# ProPrj_MP2456_2024-10-30_10-07-32_2024-1.net
KiCad netlist of a schematic drawn in EasyEDA Pro
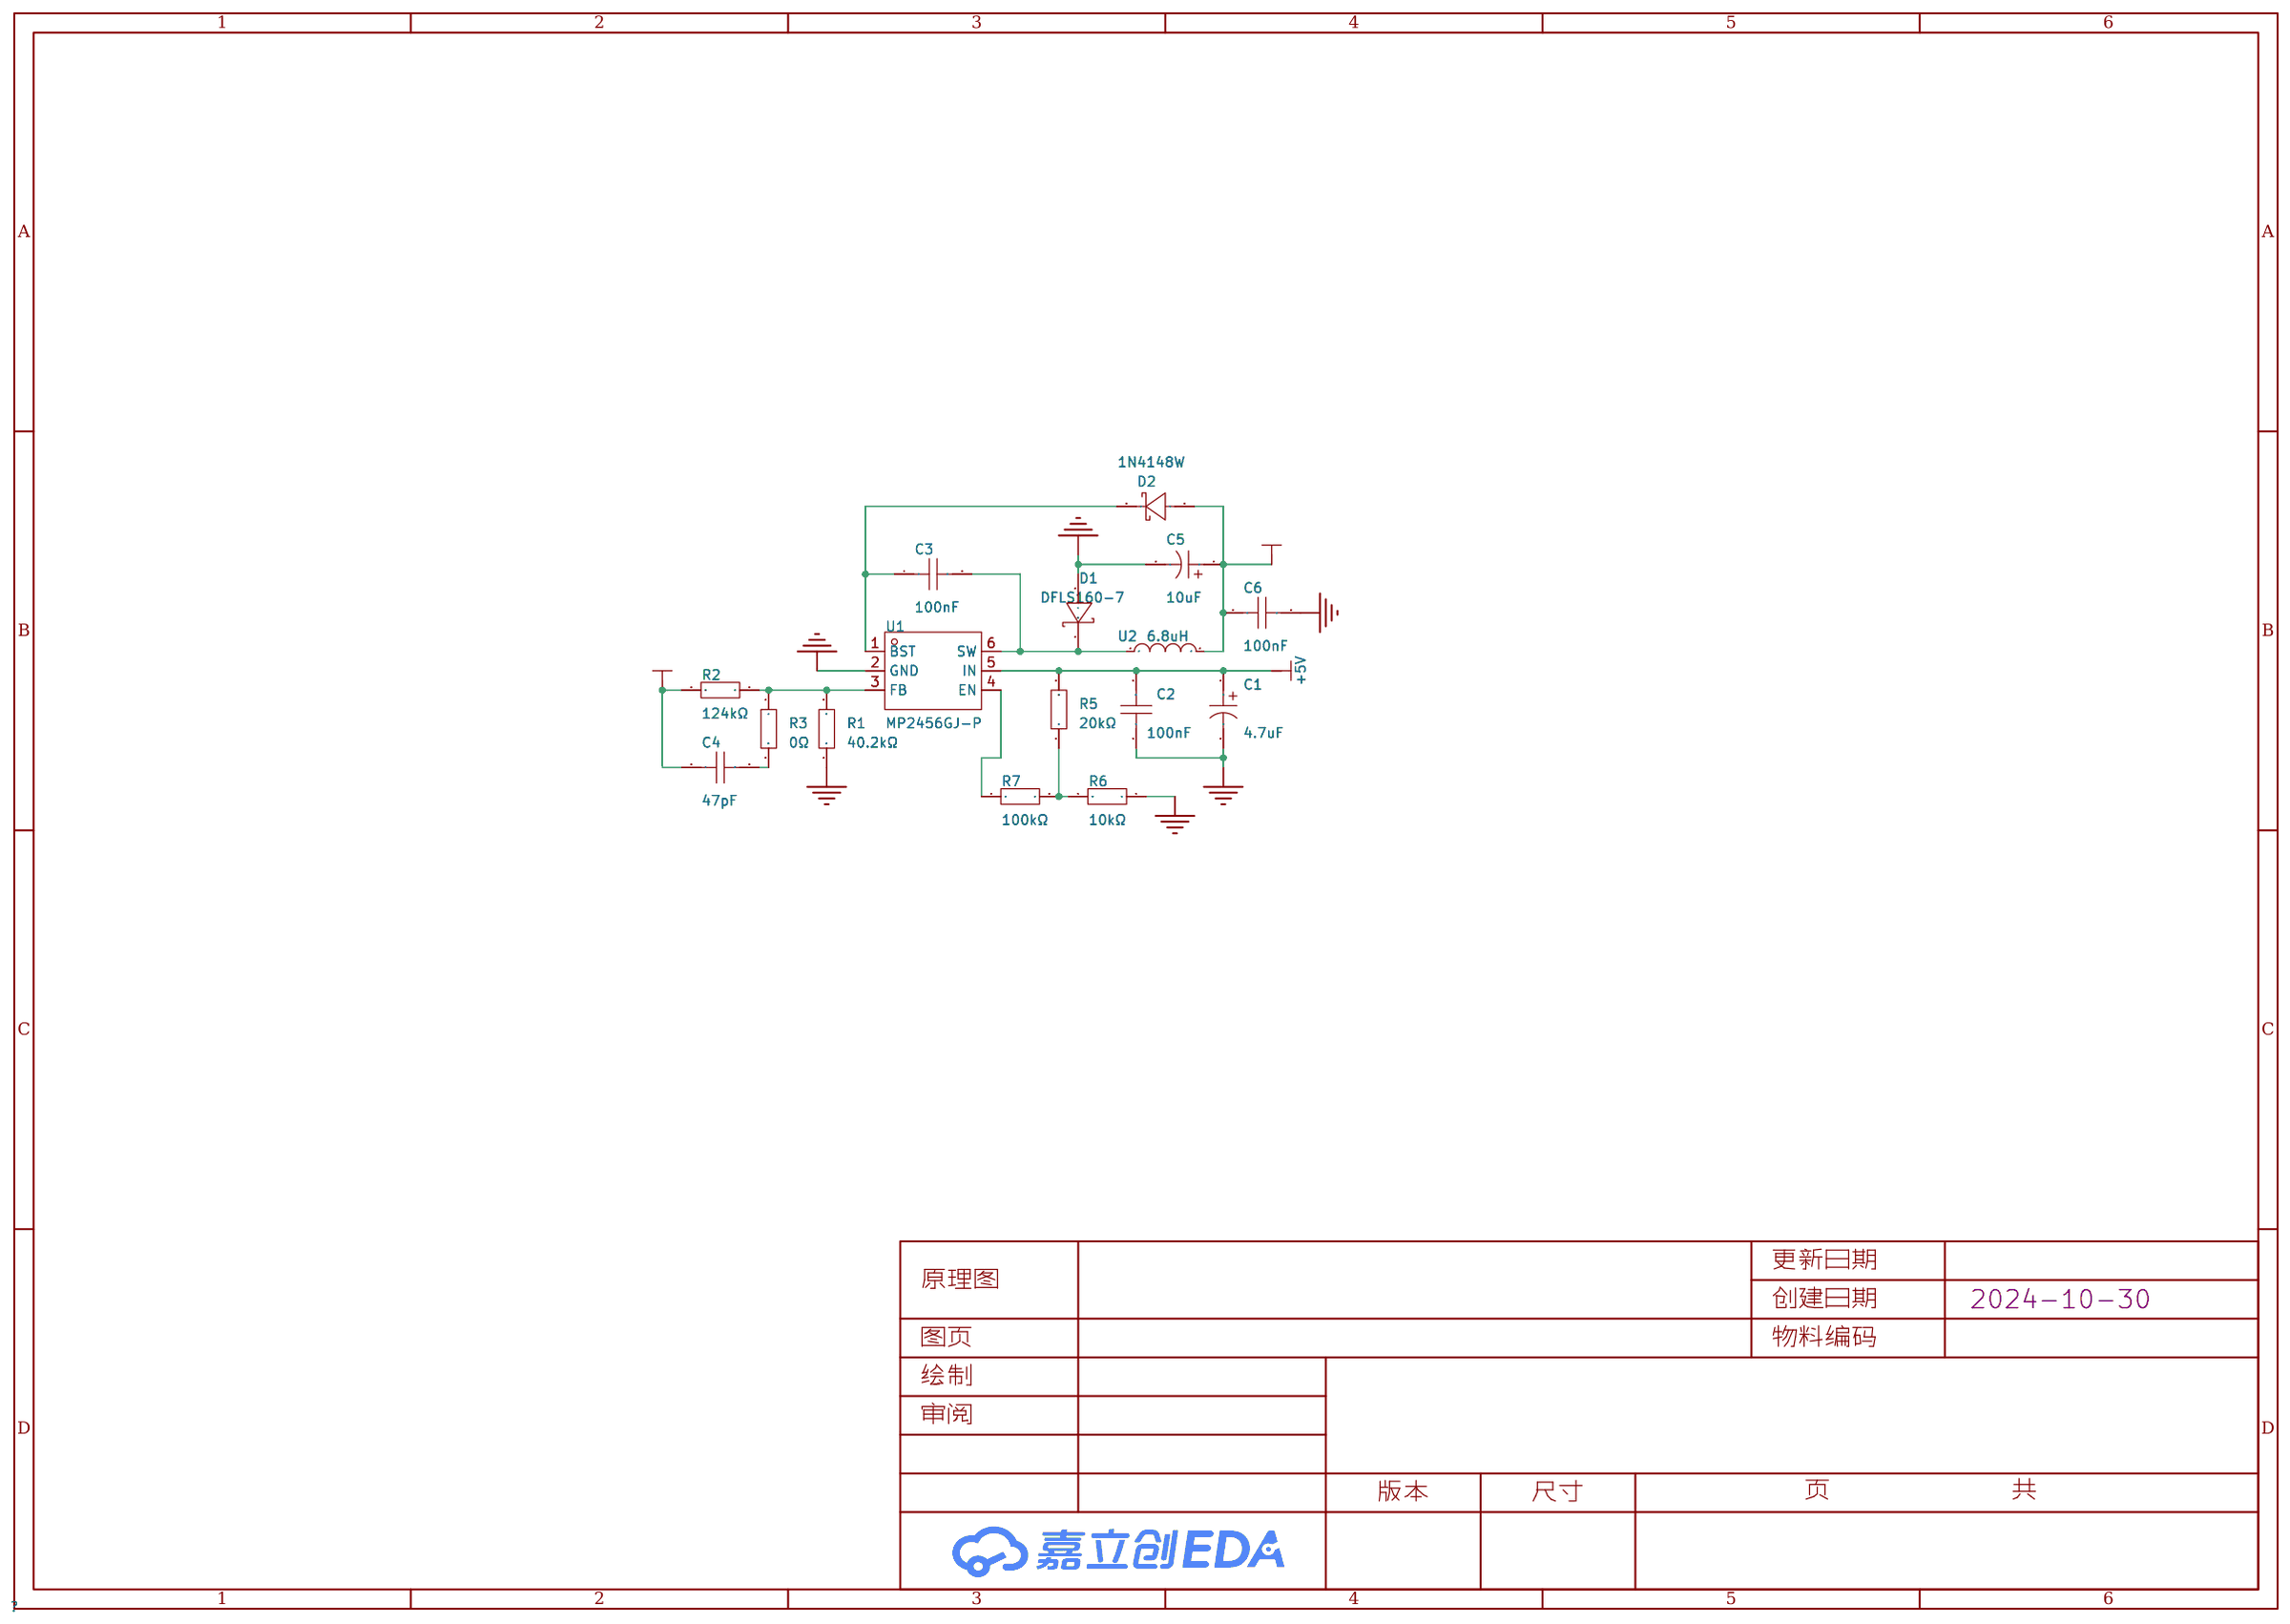
[diagram p0: schematic sheet]

(export (version "E")
  (design (tool "Eeschema 10.0.6"))
  (components
    (comp (ref "C1")
      (value "4.7uF")
      (footprint "easyedapro:CAP-SMD_L3.5-W2.8")
      (description "容值:4.7uF;精度:±10%;额定电压:16V;等效串联电阻:3.5Ω@100kHz;")
      (fields
        (field (name "Manufacturer Part") "CA45-B-16V-4.7μF-K")
        (field (name "Manufacturer") "TORCH(火炬)")
      )
      (libsource (lib "easyedapro") (part "CA45-B-16V-4.7μF-K"))
    )
    (comp (ref "C2")
      (value "100nF")
      (footprint "easyedapro:C0603")
      (description "容值:100nF;精度:±10%;额定电压:50V;材质(温度系数):X7R;")
      (fields
        (field (name "Manufacturer Part") "CGA0603X7R104K500JT")
        (field (name "Manufacturer") "HRE(芯声)")
      )
      (libsource (lib "easyedapro") (part "cga0603x7r104k500jt"))
    )
    (comp (ref "C3")
      (value "100nF")
      (footprint "easyedapro:C0603")
      (fields
        (field (name "Manufacturer Part") "CGA0603X7R104K500JT")
        (field (name "Manufacturer") "HRE(芯声)")
      )
      (libsource (lib "easyedapro") (part "CapAcitance"))
    )
    (comp (ref "C4")
      (value "47pF")
      (footprint "easyedapro:C0603")
      (fields
        (field (name "Manufacturer Part") "CL10C470JB8NNNC")
        (field (name "Manufacturer") "SAMSUNG(三星)")
      )
      (libsource (lib "easyedapro") (part "CapAcitance"))
    )
    (comp (ref "C5")
      (value "10uF")
      (footprint "easyedapro:CAP-SMD_L3.5-W2.8")
      (description "容值:4.7uF;精度:±10%;额定电压:16V;等效串联电阻:3.5Ω@100kHz;")
      (fields (field (name "Manufacturer Part") "TAJA106K016SNJ") (field (name "Manufacturer") "Kyocera AVX"))
      (libsource (lib "easyedapro") (part "CA45-B-16V-4.7μF-K"))
    )
    (comp (ref "C6")
      (value "100nF")
      (footprint "easyedapro:C0603")
      (fields
        (field (name "Manufacturer Part") "CGA0603X7R104K500JT")
        (field (name "Manufacturer") "HRE(芯声)")
      )
      (libsource (lib "easyedapro") (part "CapAcitance"))
    )
    (comp (ref "D1")
      (value "DFLS160-7")
      (footprint "easyedapro:POWERDI-123_L2.8-W1.8-LS3.7-RD")
      (description "正向压降(Vf):500mV@1A;直流反向耐压(Vr):60V;平均整流电流(Io):1A;")
      (fields (field (name "Manufacturer") "DIODES(美台)"))
      (libsource (lib "easyedapro") (part "DFLS160-7"))
    )
    (comp (ref "D2")
      (value "1N4148W")
      (footprint "easyedapro:SOD-123_L2.7-W1.6-LS3.7-FD")
      (description "二极管配置:独立式;正向压降(Vf):1.25V@150mA;直流反向耐压(Vr):100V;平均整流电流(Io):150mA;功率:400mW;反向恢复时间(trr):4ns;")
      (fields (field (name "Manufacturer") "宏迦橙"))
      (libsource (lib "easyedapro") (part "1N4148W_C7420318"))
    )
    (comp (ref "R1")
      (value "40.2kΩ")
      (footprint "easyedapro:R0603")
      (fields (field (name "Manufacturer Part") "RT0603BRD0740K2L") (field (name "Manufacturer") "YAGEO(国巨)"))
      (libsource (lib "easyedapro") (part "电阻"))
    )
    (comp (ref "R2")
      (value "124kΩ")
      (footprint "easyedapro:R0603")
      (fields
        (field (name "Manufacturer Part") "0603WAF1243T5E")
        (field (name "Manufacturer") "UNI-ROYAL(厚声)")
      )
      (libsource (lib "easyedapro") (part "电阻"))
    )
    (comp (ref "R3")
      (value "0Ω")
      (footprint "easyedapro:R0603")
      (fields
        (field (name "Manufacturer Part") "0603WAF0000T5E")
        (field (name "Manufacturer") "UNI-ROYAL(厚声)")
      )
      (libsource (lib "easyedapro") (part "电阻"))
    )
    (comp (ref "R5")
      (value "20kΩ")
      (footprint "easyedapro:R0603")
      (fields
        (field (name "Manufacturer Part") "0603WAF2002T5E")
        (field (name "Manufacturer") "UNI-ROYAL(厚声)")
      )
      (libsource (lib "easyedapro") (part "电阻"))
    )
    (comp (ref "R6")
      (value "10kΩ")
      (footprint "easyedapro:R0603")
      (fields
        (field (name "Manufacturer Part") "0603WAF1002T5E")
        (field (name "Manufacturer") "UNI-ROYAL(厚声)")
      )
      (libsource (lib "easyedapro") (part "电阻"))
    )
    (comp (ref "R7")
      (value "100kΩ")
      (footprint "easyedapro:R0603")
      (fields
        (field (name "Manufacturer Part") "0603WAF1003T5E")
        (field (name "Manufacturer") "UNI-ROYAL(厚声)")
      )
      (libsource (lib "easyedapro") (part "电阻"))
    )
    (comp (ref "U1")
      (value "MP2456GJ-P")
      (footprint "easyedapro:TSOT-23-6_L2.9-W1.6-P0.95-LS2.8-BR")
      (description "功能类型:降压型;输出类型:可调;输入电压:4.5V~50V;输出电压:810mV~45V;输出电流:500mA;")
      (fields (field (name "Manufacturer") "MPS(芯源)"))
      (libsource (lib "easyedapro") (part "mp2456gj-p"))
    )
    (comp (ref "U2")
      (value "6.8uH")
      (footprint "easyedapro:IND-SMD_L2.5-W2.0")
      (description "电感值:4.7uH;精度:±20%;额定电流:1.8A;饱和电流(Isat):2.4A;类型:一体成型电感;")
      (fields
        (field (name "Manufacturer Part") "FTC252012S6R8MBCA")
        (field (name "Manufacturer") "cjiang(长江微电)")
      )
      (libsource (lib "easyedapro") (part "FTC252012S4R7MBCA"))
    )
  )
  (nets
    (net (code "1") (name "+5V") (class "Default")
      (node (ref "C1") (pin "1") (pinfunction "1_1") (pintype "input"))
      (node (ref "C2") (pin "2") (pinfunction "2_2") (pintype "unspecified"))
      (node (ref "R5") (pin "2") (pinfunction "2_2") (pintype "input"))
      (node (ref "U1") (pin "5") (pinfunction "IN_5") (pintype "unspecified"))
    )
    (net (code "2") (name "3.3V") (class "Default")
      (node (ref "C4") (pin "1") (pinfunction "1_1") (pintype "input"))
      (node (ref "C5") (pin "1") (pinfunction "1_1") (pintype "input"))
      (node (ref "C6") (pin "1") (pinfunction "1_1") (pintype "input"))
      (node (ref "D2") (pin "1") (pinfunction "A_1") (pintype "unspecified"))
      (node (ref "R2") (pin "2") (pinfunction "2_2") (pintype "input"))
      (node (ref "U2") (pin "2") (pinfunction "2_2") (pintype "unspecified"))
    )
    (net (code "3") (name "GND") (class "Default")
      (node (ref "C1") (pin "2") (pinfunction "2_2") (pintype "input"))
      (node (ref "C2") (pin "1") (pinfunction "1_1") (pintype "unspecified"))
      (node (ref "C5") (pin "2") (pinfunction "2_2") (pintype "input"))
      (node (ref "C6") (pin "2") (pinfunction "2_2") (pintype "input"))
      (node (ref "D1") (pin "2") (pinfunction "A_2") (pintype "input"))
      (node (ref "R1") (pin "1") (pinfunction "1_1") (pintype "input"))
      (node (ref "R6") (pin "1") (pinfunction "1_1") (pintype "input"))
      (node (ref "U1") (pin "2") (pinfunction "GND_2") (pintype "unspecified"))
    )
    (net (code "4") (name "Net-(C4-Pad2)") (class "Default")
      (node (ref "C4") (pin "2") (pinfunction "2_2") (pintype "input"))
      (node (ref "R3") (pin "2") (pinfunction "2_2") (pintype "input"))
    )
    (net (code "5") (name "Net-(D1-C)") (class "Default")
      (node (ref "C3") (pin "2") (pinfunction "2_2") (pintype "input"))
      (node (ref "D1") (pin "1") (pinfunction "C_1") (pintype "input"))
      (node (ref "U1") (pin "6") (pinfunction "SW_6") (pintype "unspecified"))
      (node (ref "U2") (pin "1") (pinfunction "1_1") (pintype "unspecified"))
    )
    (net (code "6") (name "Net-(D2-K)") (class "Default")
      (node (ref "C3") (pin "1") (pinfunction "1_1") (pintype "input"))
      (node (ref "D2") (pin "2") (pinfunction "K_2") (pintype "unspecified"))
      (node (ref "U1") (pin "1") (pinfunction "BST_1") (pintype "unspecified"))
    )
    (net (code "7") (name "Net-(R5-Pad1)") (class "Default")
      (node (ref "R5") (pin "1") (pinfunction "1_1") (pintype "input"))
      (node (ref "R6") (pin "2") (pinfunction "2_2") (pintype "input"))
      (node (ref "R7") (pin "2") (pinfunction "2_2") (pintype "input"))
    )
    (net (code "8") (name "Net-(U1-EN)") (class "Default")
      (node (ref "R7") (pin "1") (pinfunction "1_1") (pintype "input"))
      (node (ref "U1") (pin "4") (pinfunction "EN_4") (pintype "unspecified"))
    )
    (net (code "9") (name "Net-(U1-FB)") (class "Default")
      (node (ref "R1") (pin "2") (pinfunction "2_2") (pintype "input"))
      (node (ref "R2") (pin "1") (pinfunction "1_1") (pintype "input"))
      (node (ref "R3") (pin "1") (pinfunction "1_1") (pintype "input"))
      (node (ref "U1") (pin "3") (pinfunction "FB_3") (pintype "unspecified"))
    )
  )
)
